# TinyG3DPrinterController.net
KiCad netlist of a schematic drawn in EAGLE
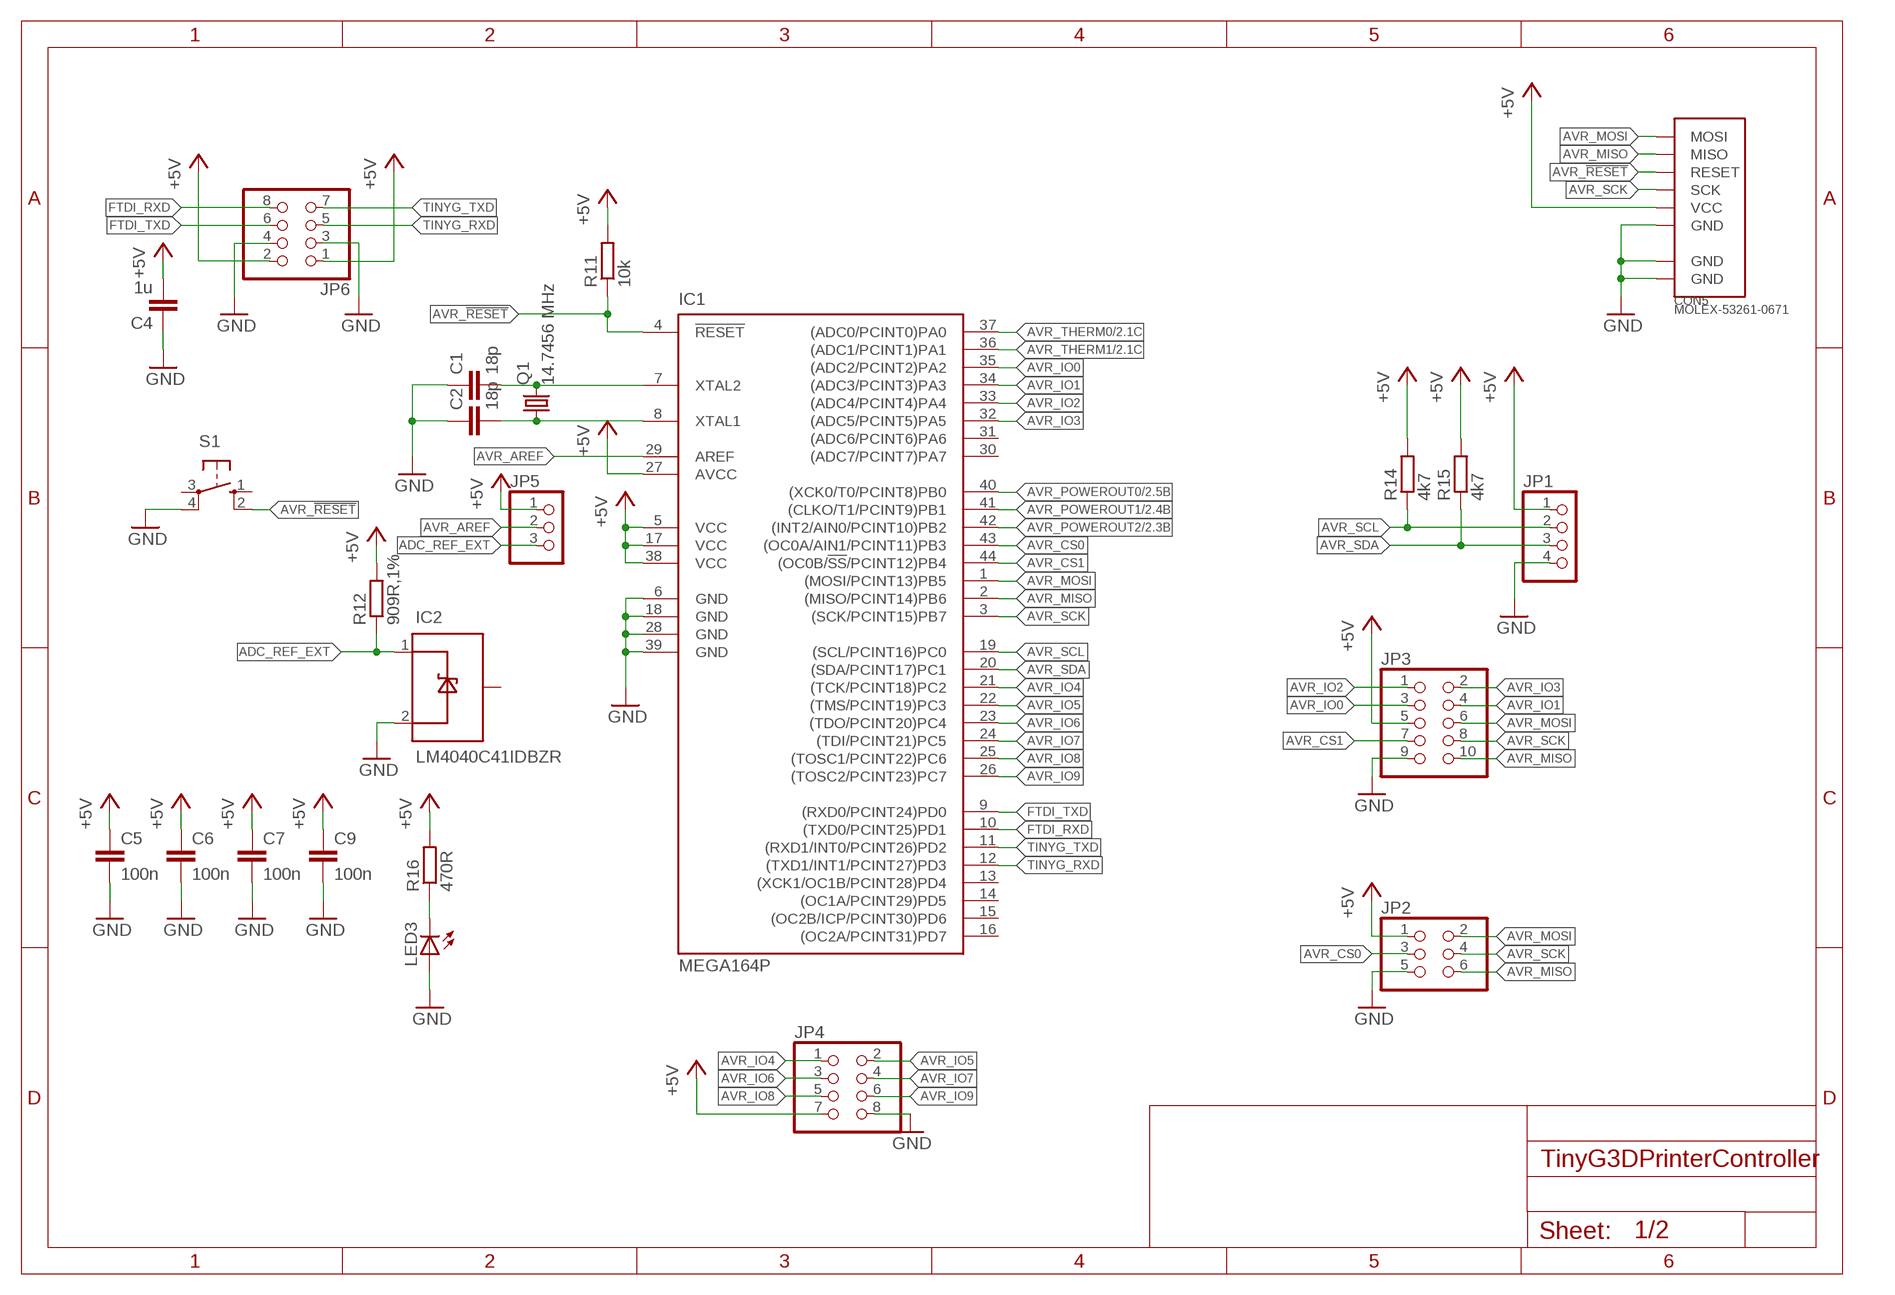
[diagram p0: schematic, sheet 1]
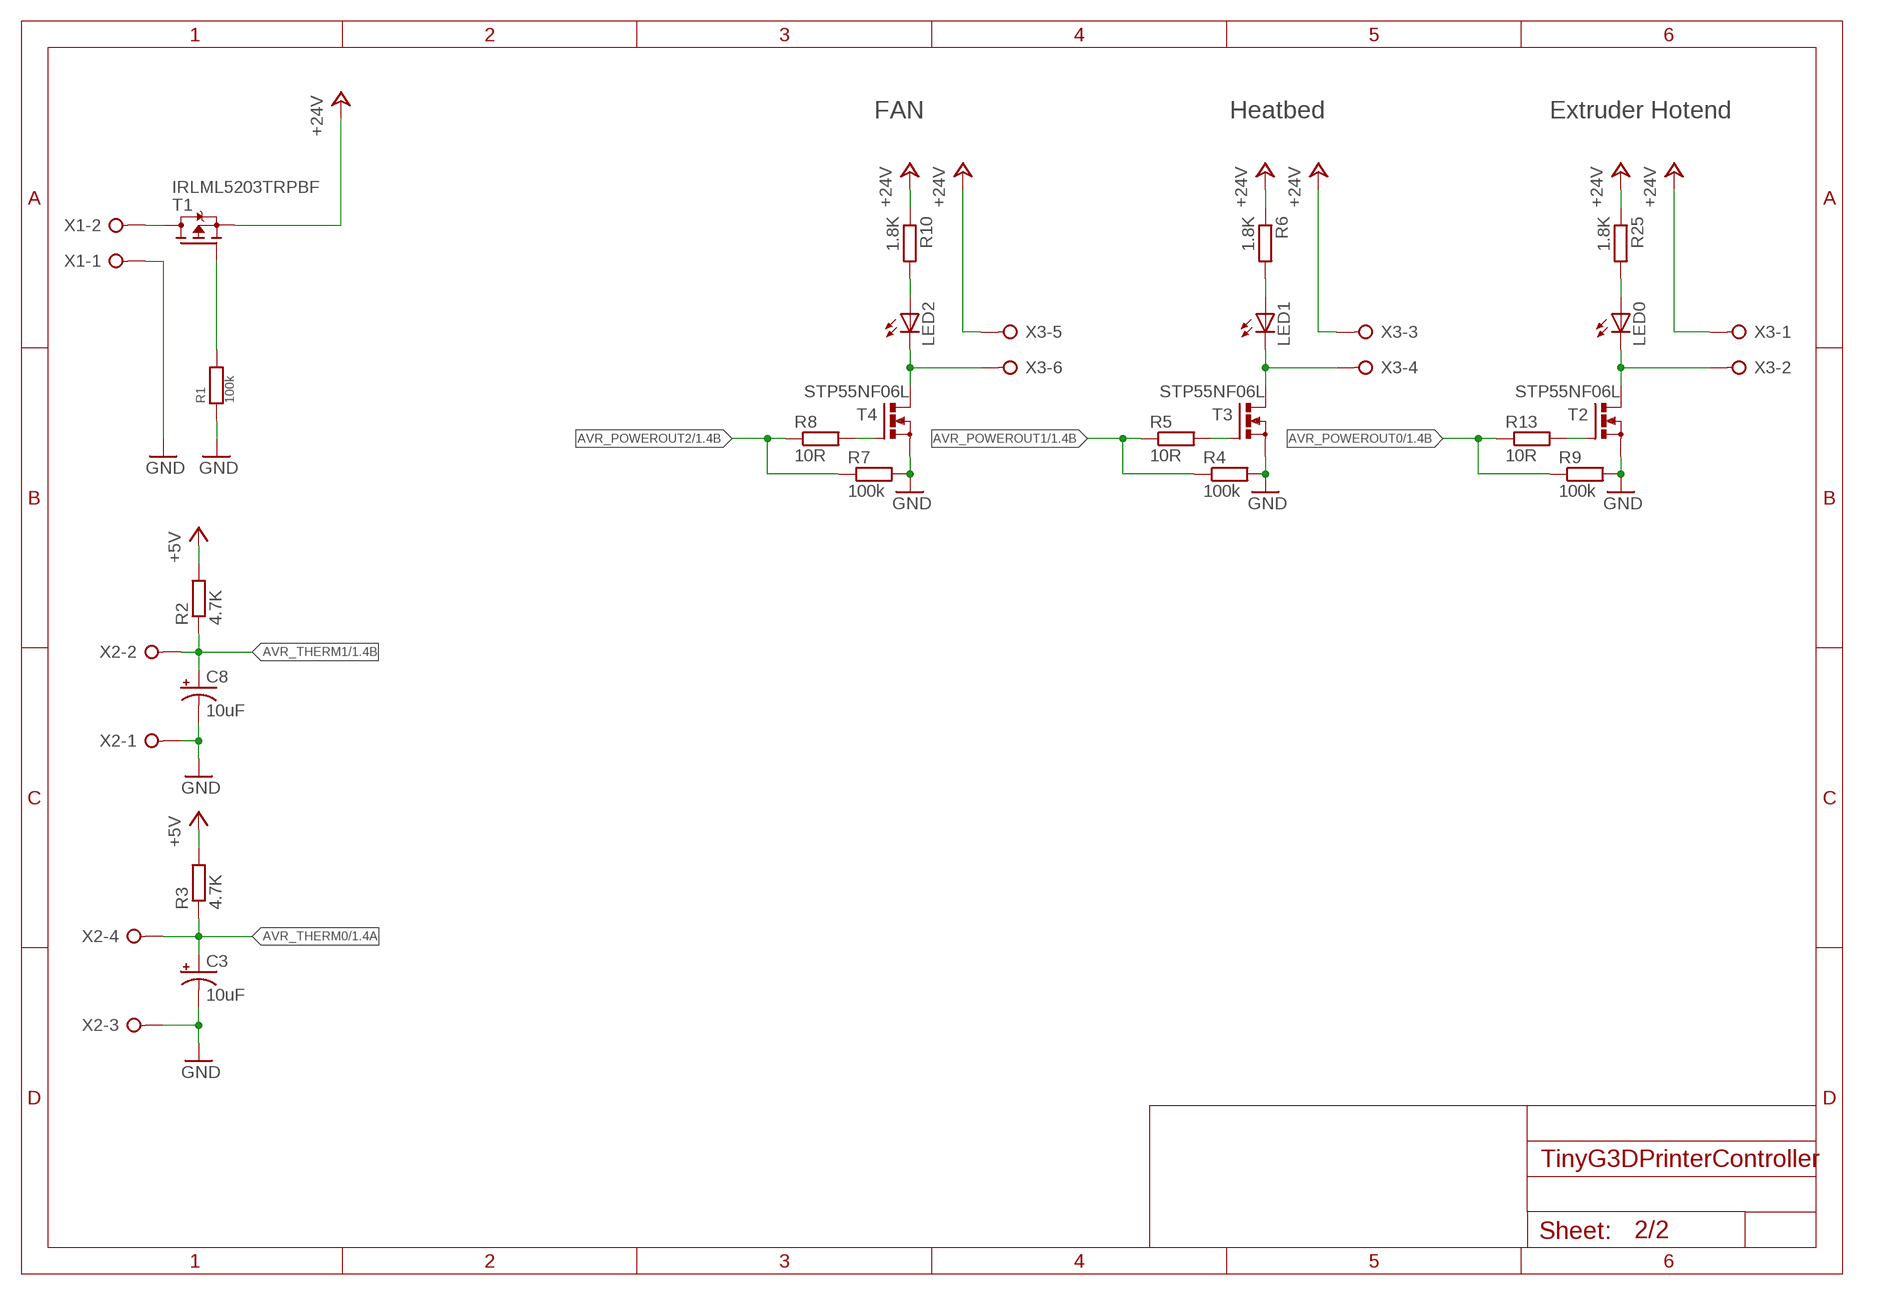
[diagram p1: schematic, sheet 2]

(export (version "E")
  (design (tool "Eeschema 10.0.6"))
  (components
    (comp (ref "C1")
      (value "18p")
      (footprint "eagle-import:C0603K")
      (libsource (lib "eagle-import") (part "C-EUC0603K"))
    )
    (comp (ref "C2")
      (value "18p")
      (footprint "eagle-import:C0603K")
      (libsource (lib "eagle-import") (part "C-EUC0603K"))
    )
    (comp (ref "C4")
      (value "1u")
      (footprint "eagle-import:C1206K")
      (libsource (lib "eagle-import") (part "C-EUC1206K"))
    )
    (comp (ref "C5")
      (value "100n")
      (footprint "eagle-import:C0603K")
      (libsource (lib "eagle-import") (part "C-EUC0603K"))
    )
    (comp (ref "C6")
      (value "100n")
      (footprint "eagle-import:C0603K")
      (libsource (lib "eagle-import") (part "C-EUC0603K"))
    )
    (comp (ref "C7")
      (value "100n")
      (footprint "eagle-import:C0603K")
      (libsource (lib "eagle-import") (part "C-EUC0603K"))
    )
    (comp (ref "C9")
      (value "100n")
      (footprint "eagle-import:C0603K")
      (libsource (lib "eagle-import") (part "C-EUC0603K"))
    )
    (comp (ref "CON5")
      (value "MOLEX-53261-0671")
      (footprint "eagle-import:MOLEX-53261-0671")
      (libsource (lib "eagle-import") (part "MOLEX-53261-0671"))
    )
    (comp (ref "IC1")
      (value "MEGA164P")
      (footprint "eagle-import:TQFP44")
      (libsource (lib "eagle-import") (part "MEGA164P/324P/644P-AU"))
    )
    (comp (ref "IC2")
      (value "LM4040C41IDBZR")
      (footprint "eagle-import:SOT-23-3")
      (libsource (lib "eagle-import") (part "LM4040C41IDBZR"))
    )
    (comp (ref "JP1")
      (value "PINHD-1X4")
      (footprint "eagle-import:1X04")
      (libsource (lib "eagle-import") (part "PINHD-1X4"))
    )
    (comp (ref "JP2")
      (value "PINHD-2X3")
      (footprint "eagle-import:2X03")
      (libsource (lib "eagle-import") (part "PINHD-2X3"))
    )
    (comp (ref "JP3")
      (value "PINHD-2X5")
      (footprint "eagle-import:2X05")
      (libsource (lib "eagle-import") (part "PINHD-2X5"))
    )
    (comp (ref "JP4")
      (value "PINHD-2X4")
      (footprint "eagle-import:2X04")
      (libsource (lib "eagle-import") (part "PINHD-2X4"))
    )
    (comp (ref "JP5")
      (value "PINHD-1X3")
      (footprint "eagle-import:1X03")
      (libsource (lib "eagle-import") (part "PINHD-1X3"))
    )
    (comp (ref "JP6")
      (value "PINHD-2X4")
      (footprint "eagle-import:2X04")
      (libsource (lib "eagle-import") (part "PINHD-2X4"))
    )
    (comp (ref "LED3")
      (value "LEDCHIP-LED0805")
      (footprint "eagle-import:CHIP-LED0805")
      (libsource (lib "eagle-import") (part "LEDCHIP-LED0805"))
    )
    (comp (ref "Q1")
      (value "14.7456 MHz")
      (footprint "eagle-import:CRYSTAL_2P_5MMX3.2MM")
      (libsource (lib "eagle-import") (part "7A-14.7456MAAJ-T-SMD_CRYSTAL"))
    )
    (comp (ref "R11")
      (value "10k")
      (footprint "eagle-import:R0603")
      (libsource (lib "eagle-import") (part "R-EU_R0603"))
    )
    (comp (ref "R12")
      (value "909R,1%")
      (footprint "eagle-import:R0603")
      (libsource (lib "eagle-import") (part "R-EU_R0603"))
    )
    (comp (ref "R14")
      (value "4k7")
      (footprint "eagle-import:R0603")
      (libsource (lib "eagle-import") (part "R-EU_R0603"))
    )
    (comp (ref "R15")
      (value "4k7")
      (footprint "eagle-import:R0603")
      (libsource (lib "eagle-import") (part "R-EU_R0603"))
    )
    (comp (ref "R16")
      (value "470R")
      (footprint "eagle-import:R0603")
      (libsource (lib "eagle-import") (part "R-EU_R0603"))
    )
    (comp (ref "S1")
      (value "10-XX")
      (footprint "eagle-import:B3F-10XX")
      (fields (field (name "MPN") "B3F-1000"))
      (libsource (lib "eagle-import") (part "10-XX"))
    )
    (comp (ref "C3")
      (value "10uF")
      (footprint "eagle-import:153CLV-0405")
      (libsource (lib "eagle-import") (part "CPOL-US153CLV-0405"))
    )
    (comp (ref "C8")
      (value "10uF")
      (footprint "eagle-import:153CLV-0405")
      (libsource (lib "eagle-import") (part "CPOL-US153CLV-0405"))
    )
    (comp (ref "LED0")
      (value "LEDCHIP-LED0805")
      (footprint "eagle-import:CHIP-LED0805")
      (libsource (lib "eagle-import") (part "LEDCHIP-LED0805"))
    )
    (comp (ref "LED1")
      (value "LEDCHIP-LED0805")
      (footprint "eagle-import:CHIP-LED0805")
      (libsource (lib "eagle-import") (part "LEDCHIP-LED0805"))
    )
    (comp (ref "LED2")
      (value "LEDCHIP-LED0805")
      (footprint "eagle-import:CHIP-LED0805")
      (libsource (lib "eagle-import") (part "LEDCHIP-LED0805"))
    )
    (comp (ref "R1")
      (value "100k")
      (footprint "eagle-import:R0603")
      (libsource (lib "eagle-import") (part "R0603"))
    )
    (comp (ref "R2")
      (value "4.7K")
      (footprint "eagle-import:R0603")
      (libsource (lib "eagle-import") (part "R-EU_R0603"))
    )
    (comp (ref "R3")
      (value "4.7K")
      (footprint "eagle-import:R0603")
      (libsource (lib "eagle-import") (part "R-EU_R0603"))
    )
    (comp (ref "R4")
      (value "100k")
      (footprint "eagle-import:R0603")
      (libsource (lib "eagle-import") (part "R-EU_R0603"))
    )
    (comp (ref "R5")
      (value "10R")
      (footprint "eagle-import:R0603")
      (libsource (lib "eagle-import") (part "R-EU_R0603"))
    )
    (comp (ref "R6")
      (value "1.8K")
      (footprint "eagle-import:R0603")
      (libsource (lib "eagle-import") (part "R-EU_R0603"))
    )
    (comp (ref "R7")
      (value "100k")
      (footprint "eagle-import:R0603")
      (libsource (lib "eagle-import") (part "R-EU_R0603"))
    )
    (comp (ref "R8")
      (value "10R")
      (footprint "eagle-import:R0603")
      (libsource (lib "eagle-import") (part "R-EU_R0603"))
    )
    (comp (ref "R9")
      (value "100k")
      (footprint "eagle-import:R0603")
      (libsource (lib "eagle-import") (part "R-EU_R0603"))
    )
    (comp (ref "R10")
      (value "1.8K")
      (footprint "eagle-import:R0603")
      (libsource (lib "eagle-import") (part "R-EU_R0603"))
    )
    (comp (ref "R13")
      (value "10R")
      (footprint "eagle-import:R0603")
      (libsource (lib "eagle-import") (part "R-EU_R0603"))
    )
    (comp (ref "R25")
      (value "1.8K")
      (footprint "eagle-import:R0603")
      (libsource (lib "eagle-import") (part "R-EU_R0603"))
    )
    (comp (ref "T1")
      (value "IRLML5203TRPBF")
      (footprint "eagle-import:SOT23")
      (libsource (lib "eagle-import") (part "IRLML5203TRPBF"))
    )
    (comp (ref "T2")
      (value "STP55NF06L")
      (footprint "eagle-import:TO220BV")
      (libsource (lib "eagle-import") (part "IRF512"))
    )
    (comp (ref "T3")
      (value "STP55NF06L")
      (footprint "eagle-import:TO220BV")
      (libsource (lib "eagle-import") (part "IRF512"))
    )
    (comp (ref "T4")
      (value "STP55NF06L")
      (footprint "eagle-import:TO220BV")
      (libsource (lib "eagle-import") (part "IRF512"))
    )
    (comp (ref "X1")
      (value "W237-02P")
      (footprint "eagle-import:W237-132")
      (libsource (lib "eagle-import") (part "W237-02P"))
    )
    (comp (ref "X2")
      (value "W237-04P")
      (footprint "eagle-import:W237-4P")
      (libsource (lib "eagle-import") (part "W237-04P"))
    )
    (comp (ref "X3")
      (value "W237-06P")
      (footprint "eagle-import:W237-6P")
      (libsource (lib "eagle-import") (part "W237-06P"))
    )
  )
  (nets
    (net (code "1") (name "+5V") (class "Default")
      (node (ref "C4") (pin "2") (pinfunction "2_2") (pintype "passive"))
      (node (ref "C5") (pin "1") (pinfunction "1_1") (pintype "passive"))
      (node (ref "C6") (pin "1") (pinfunction "1_1") (pintype "passive"))
      (node (ref "C7") (pin "1") (pinfunction "1_1") (pintype "passive"))
      (node (ref "C9") (pin "1") (pinfunction "1_1") (pintype "passive"))
      (node (ref "CON5") (pin "5") (pinfunction "VCC_5") (pintype "bidirectional"))
      (node (ref "IC1") (pin "17") (pinfunction "VCC_17") (pintype "power_in"))
      (node (ref "IC1") (pin "27") (pinfunction "AVCC_27") (pintype "power_in"))
      (node (ref "IC1") (pin "38") (pinfunction "VCC_38") (pintype "power_in"))
      (node (ref "IC1") (pin "5") (pinfunction "VCC_5") (pintype "power_in"))
      (node (ref "JP1") (pin "1") (pinfunction "1_1") (pintype "passive"))
      (node (ref "JP2") (pin "1") (pinfunction "1_1") (pintype "passive"))
      (node (ref "JP3") (pin "5") (pinfunction "5_5") (pintype "passive"))
      (node (ref "JP4") (pin "7") (pinfunction "7_7") (pintype "passive"))
      (node (ref "JP5") (pin "1") (pinfunction "1_1") (pintype "passive"))
      (node (ref "JP6") (pin "1") (pinfunction "1_1") (pintype "passive"))
      (node (ref "JP6") (pin "2") (pinfunction "2_2") (pintype "passive"))
      (node (ref "R11") (pin "2") (pinfunction "2_2") (pintype "passive"))
      (node (ref "R12") (pin "2") (pinfunction "2_2") (pintype "passive"))
      (node (ref "R14") (pin "2") (pinfunction "2_2") (pintype "passive"))
      (node (ref "R15") (pin "2") (pinfunction "2_2") (pintype "passive"))
      (node (ref "R16") (pin "2") (pinfunction "2_2") (pintype "passive"))
      (node (ref "R2") (pin "2") (pinfunction "2_2") (pintype "passive"))
      (node (ref "R3") (pin "2") (pinfunction "2_2") (pintype "passive"))
    )
    (net (code "2") (name "+24V") (class "Default")
      (node (ref "R10") (pin "1") (pinfunction "1_1") (pintype "passive"))
      (node (ref "R25") (pin "1") (pinfunction "1_1") (pintype "passive"))
      (node (ref "R6") (pin "1") (pinfunction "1_1") (pintype "passive"))
      (node (ref "T1") (pin "2") (pinfunction "S_2") (pintype "passive"))
      (node (ref "X3") (pin "1") (pinfunction "KL_1") (pintype "passive"))
      (node (ref "X3") (pin "3") (pinfunction "KL_3") (pintype "passive"))
      (node (ref "X3") (pin "5") (pinfunction "KL_5") (pintype "passive"))
    )
    (net (code "3") (name "ADC_REF_EXT") (class "Default")
      (node (ref "IC2") (pin "1") (pinfunction "1_1") (pintype "bidirectional"))
      (node (ref "JP5") (pin "3") (pinfunction "3_3") (pintype "passive"))
      (node (ref "R12") (pin "1") (pinfunction "1_1") (pintype "passive"))
    )
    (net (code "4") (name "AVR_AREF") (class "Default")
      (node (ref "IC1") (pin "29") (pinfunction "AREF_29") (pintype "power_in"))
      (node (ref "JP5") (pin "2") (pinfunction "2_2") (pintype "passive"))
    )
    (net (code "5") (name "AVR_CS0") (class "Default")
      (node (ref "IC1") (pin "43") (pinfunction "(OC0A/AIN1/PCINT11)PB3_43") (pintype "bidirectional"))
      (node (ref "JP2") (pin "3") (pinfunction "3_3") (pintype "passive"))
    )
    (net (code "6") (name "AVR_CS1") (class "Default")
      (node (ref "IC1") (pin "44") (pinfunction "(OC0B/~{SS}/PCINT12)PB4_44") (pintype "bidirectional"))
      (node (ref "JP3") (pin "7") (pinfunction "7_7") (pintype "passive"))
    )
    (net (code "7") (name "AVR_IO0") (class "Default")
      (node (ref "IC1") (pin "35") (pinfunction "(ADC2/PCINT2)PA2_35") (pintype "bidirectional"))
      (node (ref "JP3") (pin "3") (pinfunction "3_3") (pintype "passive"))
    )
    (net (code "8") (name "AVR_IO1") (class "Default")
      (node (ref "IC1") (pin "34") (pinfunction "(ADC3/PCINT3)PA3_34") (pintype "bidirectional"))
      (node (ref "JP3") (pin "4") (pinfunction "4_4") (pintype "passive"))
    )
    (net (code "9") (name "AVR_IO2") (class "Default")
      (node (ref "IC1") (pin "33") (pinfunction "(ADC4/PCINT4)PA4_33") (pintype "bidirectional"))
      (node (ref "JP3") (pin "1") (pinfunction "1_1") (pintype "passive"))
    )
    (net (code "10") (name "AVR_IO3") (class "Default")
      (node (ref "IC1") (pin "32") (pinfunction "(ADC5/PCINT5)PA5_32") (pintype "bidirectional"))
      (node (ref "JP3") (pin "2") (pinfunction "2_2") (pintype "passive"))
    )
    (net (code "11") (name "AVR_IO4") (class "Default")
      (node (ref "IC1") (pin "21") (pinfunction "(TCK/PCINT18)PC2_21") (pintype "bidirectional"))
      (node (ref "JP4") (pin "1") (pinfunction "1_1") (pintype "passive"))
    )
    (net (code "12") (name "AVR_IO5") (class "Default")
      (node (ref "IC1") (pin "22") (pinfunction "(TMS/PCINT19)PC3_22") (pintype "bidirectional"))
      (node (ref "JP4") (pin "2") (pinfunction "2_2") (pintype "passive"))
    )
    (net (code "13") (name "AVR_IO6") (class "Default")
      (node (ref "IC1") (pin "23") (pinfunction "(TDO/PCINT20)PC4_23") (pintype "bidirectional"))
      (node (ref "JP4") (pin "3") (pinfunction "3_3") (pintype "passive"))
    )
    (net (code "14") (name "AVR_IO7") (class "Default")
      (node (ref "IC1") (pin "24") (pinfunction "(TDI/PCINT21)PC5_24") (pintype "bidirectional"))
      (node (ref "JP4") (pin "4") (pinfunction "4_4") (pintype "passive"))
    )
    (net (code "15") (name "AVR_IO8") (class "Default")
      (node (ref "IC1") (pin "25") (pinfunction "(TOSC1/PCINT22)PC6_25") (pintype "bidirectional"))
      (node (ref "JP4") (pin "5") (pinfunction "5_5") (pintype "passive"))
    )
    (net (code "16") (name "AVR_IO9") (class "Default")
      (node (ref "IC1") (pin "26") (pinfunction "(TOSC2/PCINT23)PC7_26") (pintype "bidirectional"))
      (node (ref "JP4") (pin "6") (pinfunction "6_6") (pintype "passive"))
    )
    (net (code "17") (name "AVR_MISO") (class "Default")
      (node (ref "CON5") (pin "2") (pinfunction "MISO_2") (pintype "bidirectional"))
      (node (ref "IC1") (pin "2") (pinfunction "(MISO/PCINT14)PB6_2") (pintype "bidirectional"))
      (node (ref "JP2") (pin "6") (pinfunction "6_6") (pintype "passive"))
      (node (ref "JP3") (pin "10") (pinfunction "10_10") (pintype "passive"))
    )
    (net (code "18") (name "AVR_MOSI") (class "Default")
      (node (ref "CON5") (pin "1") (pinfunction "MOSI_1") (pintype "bidirectional"))
      (node (ref "IC1") (pin "1") (pinfunction "(MOSI/PCINT13)PB5_1") (pintype "bidirectional"))
      (node (ref "JP2") (pin "2") (pinfunction "2_2") (pintype "passive"))
      (node (ref "JP3") (pin "6") (pinfunction "6_6") (pintype "passive"))
    )
    (net (code "19") (name "AVR_POWEROUT0") (class "Default")
      (node (ref "IC1") (pin "40") (pinfunction "(XCK0/T0/PCINT8)PB0_40") (pintype "bidirectional"))
      (node (ref "R13") (pin "1") (pinfunction "1_1") (pintype "passive"))
      (node (ref "R9") (pin "1") (pinfunction "1_1") (pintype "passive"))
    )
    (net (code "20") (name "AVR_POWEROUT1") (class "Default")
      (node (ref "IC1") (pin "41") (pinfunction "(CLKO/T1/PCINT9)PB1_41") (pintype "bidirectional"))
      (node (ref "R4") (pin "1") (pinfunction "1_1") (pintype "passive"))
      (node (ref "R5") (pin "1") (pinfunction "1_1") (pintype "passive"))
    )
    (net (code "21") (name "AVR_POWEROUT2") (class "Default")
      (node (ref "IC1") (pin "42") (pinfunction "(INT2/AIN0/PCINT10)PB2_42") (pintype "bidirectional"))
      (node (ref "R7") (pin "1") (pinfunction "1_1") (pintype "passive"))
      (node (ref "R8") (pin "1") (pinfunction "1_1") (pintype "passive"))
    )
    (net (code "22") (name "AVR_SCK") (class "Default")
      (node (ref "CON5") (pin "4") (pinfunction "SCK_4") (pintype "bidirectional"))
      (node (ref "IC1") (pin "3") (pinfunction "(SCK/PCINT15)PB7_3") (pintype "bidirectional"))
      (node (ref "JP2") (pin "4") (pinfunction "4_4") (pintype "passive"))
      (node (ref "JP3") (pin "8") (pinfunction "8_8") (pintype "passive"))
    )
    (net (code "23") (name "AVR_SCL") (class "Default")
      (node (ref "IC1") (pin "19") (pinfunction "(SCL/PCINT16)PC0_19") (pintype "bidirectional"))
      (node (ref "JP1") (pin "2") (pinfunction "2_2") (pintype "passive"))
      (node (ref "R14") (pin "1") (pinfunction "1_1") (pintype "passive"))
    )
    (net (code "24") (name "AVR_SDA") (class "Default")
      (node (ref "IC1") (pin "20") (pinfunction "(SDA/PCINT17)PC1_20") (pintype "bidirectional"))
      (node (ref "JP1") (pin "3") (pinfunction "3_3") (pintype "passive"))
      (node (ref "R15") (pin "1") (pinfunction "1_1") (pintype "passive"))
    )
    (net (code "25") (name "AVR_THERM0") (class "Default")
      (node (ref "C3") (pin "+") (pinfunction "+_+") (pintype "passive"))
      (node (ref "IC1") (pin "37") (pinfunction "(ADC0/PCINT0)PA0_37") (pintype "bidirectional"))
      (node (ref "R3") (pin "1") (pinfunction "1_1") (pintype "passive"))
      (node (ref "X2") (pin "4") (pinfunction "KL_4") (pintype "passive"))
    )
    (net (code "26") (name "AVR_THERM1") (class "Default")
      (node (ref "C8") (pin "+") (pinfunction "+_+") (pintype "passive"))
      (node (ref "IC1") (pin "36") (pinfunction "(ADC1/PCINT1)PA1_36") (pintype "bidirectional"))
      (node (ref "R2") (pin "1") (pinfunction "1_1") (pintype "passive"))
      (node (ref "X2") (pin "2") (pinfunction "KL_2") (pintype "passive"))
    )
    (net (code "27") (name "AVR_~{RESET}") (class "Default")
      (node (ref "CON5") (pin "3") (pinfunction "RESET_3") (pintype "bidirectional"))
      (node (ref "IC1") (pin "4") (pinfunction "~{RESET}_4") (pintype "input"))
      (node (ref "R11") (pin "1") (pinfunction "1_1") (pintype "passive"))
      (node (ref "S1") (pin "2") (pinfunction "S1_2") (pintype "passive"))
    )
    (net (code "28") (name "FTDI_RXD") (class "Default")
      (node (ref "IC1") (pin "10") (pinfunction "(TXD0/PCINT25)PD1_10") (pintype "bidirectional"))
      (node (ref "JP6") (pin "8") (pinfunction "8_8") (pintype "passive"))
    )
    (net (code "29") (name "FTDI_TXD") (class "Default")
      (node (ref "IC1") (pin "9") (pinfunction "(RXD0/PCINT24)PD0_9") (pintype "bidirectional"))
      (node (ref "JP6") (pin "6") (pinfunction "6_6") (pintype "passive"))
    )
    (net (code "30") (name "GND") (class "Default")
      (node (ref "C1") (pin "1") (pinfunction "1_1") (pintype "passive"))
      (node (ref "C2") (pin "1") (pinfunction "1_1") (pintype "passive"))
      (node (ref "C3") (pin "-") (pinfunction "-_-") (pintype "passive"))
      (node (ref "C4") (pin "1") (pinfunction "1_1") (pintype "passive"))
      (node (ref "C5") (pin "2") (pinfunction "2_2") (pintype "passive"))
      (node (ref "C6") (pin "2") (pinfunction "2_2") (pintype "passive"))
      (node (ref "C7") (pin "2") (pinfunction "2_2") (pintype "passive"))
      (node (ref "C8") (pin "-") (pinfunction "-_-") (pintype "passive"))
      (node (ref "C9") (pin "2") (pinfunction "2_2") (pintype "passive"))
      (node (ref "CON5") (pin "6") (pinfunction "GND_6") (pintype "bidirectional"))
      (node (ref "CON5") (pin "GND@1") (pinfunction "GND_GND@1") (pintype "power_in"))
      (node (ref "CON5") (pin "GND@2") (pinfunction "GND_GND@2") (pintype "power_in"))
      (node (ref "IC1") (pin "18") (pinfunction "GND_18") (pintype "power_in"))
      (node (ref "IC1") (pin "28") (pinfunction "GND_28") (pintype "power_in"))
      (node (ref "IC1") (pin "39") (pinfunction "GND_39") (pintype "power_in"))
      (node (ref "IC1") (pin "6") (pinfunction "GND_6") (pintype "power_in"))
      (node (ref "IC2") (pin "2") (pinfunction "2_2") (pintype "bidirectional"))
      (node (ref "JP1") (pin "4") (pinfunction "4_4") (pintype "passive"))
      (node (ref "JP2") (pin "5") (pinfunction "5_5") (pintype "passive"))
      (node (ref "JP3") (pin "9") (pinfunction "9_9") (pintype "passive"))
      (node (ref "JP4") (pin "8") (pinfunction "8_8") (pintype "passive"))
      (node (ref "JP6") (pin "3") (pinfunction "3_3") (pintype "passive"))
      (node (ref "JP6") (pin "4") (pinfunction "4_4") (pintype "passive"))
      (node (ref "LED3") (pin "A") (pinfunction "A_A") (pintype "passive"))
      (node (ref "R1") (pin "1") (pinfunction "P$1_1") (pintype "passive"))
      (node (ref "R4") (pin "2") (pinfunction "2_2") (pintype "passive"))
      (node (ref "R7") (pin "2") (pinfunction "2_2") (pintype "passive"))
      (node (ref "R9") (pin "2") (pinfunction "2_2") (pintype "passive"))
      (node (ref "S1") (pin "4") (pinfunction "P1_4") (pintype "passive"))
      (node (ref "T2") (pin "S") (pinfunction "S_S") (pintype "passive"))
      (node (ref "T3") (pin "S") (pinfunction "S_S") (pintype "passive"))
      (node (ref "T4") (pin "S") (pinfunction "S_S") (pintype "passive"))
      (node (ref "X1") (pin "1") (pinfunction "KL_1") (pintype "passive"))
      (node (ref "X2") (pin "1") (pinfunction "KL_1") (pintype "passive"))
      (node (ref "X2") (pin "3") (pinfunction "KL_3") (pintype "passive"))
    )
    (net (code "31") (name "Net-(IC1-XTAL1)") (class "Default")
      (node (ref "C2") (pin "2") (pinfunction "2_2") (pintype "passive"))
      (node (ref "IC1") (pin "8") (pinfunction "XTAL1_8") (pintype "input"))
      (node (ref "Q1") (pin "P$1") (pinfunction "1_P$1") (pintype "passive"))
    )
    (net (code "32") (name "Net-(IC1-XTAL2)") (class "Default")
      (node (ref "C1") (pin "2") (pinfunction "2_2") (pintype "passive"))
      (node (ref "IC1") (pin "7") (pinfunction "XTAL2_7") (pintype "output"))
      (node (ref "Q1") (pin "P$2") (pinfunction "2_P$2") (pintype "passive"))
    )
    (net (code "33") (name "Net-(LED0-PadA)") (class "Default")
      (node (ref "LED0") (pin "A") (pinfunction "A_A") (pintype "passive"))
      (node (ref "R25") (pin "2") (pinfunction "2_2") (pintype "passive"))
    )
    (net (code "34") (name "Net-(LED1-PadA)") (class "Default")
      (node (ref "LED1") (pin "A") (pinfunction "A_A") (pintype "passive"))
      (node (ref "R6") (pin "2") (pinfunction "2_2") (pintype "passive"))
    )
    (net (code "35") (name "Net-(LED2-PadA)") (class "Default")
      (node (ref "LED2") (pin "A") (pinfunction "A_A") (pintype "passive"))
      (node (ref "R10") (pin "2") (pinfunction "2_2") (pintype "passive"))
    )
    (net (code "36") (name "Net-(LED3-PadC)") (class "Default")
      (node (ref "LED3") (pin "C") (pinfunction "C_C") (pintype "passive"))
      (node (ref "R16") (pin "1") (pinfunction "1_1") (pintype "passive"))
    )
    (net (code "37") (name "Net-(R1-P$2)") (class "Default")
      (node (ref "R1") (pin "2") (pinfunction "P$2_2") (pintype "passive"))
      (node (ref "T1") (pin "1") (pinfunction "G_1") (pintype "passive"))
    )
    (net (code "38") (name "Net-(R5-Pad2)") (class "Default")
      (node (ref "R5") (pin "2") (pinfunction "2_2") (pintype "passive"))
      (node (ref "T3") (pin "G") (pinfunction "G_G") (pintype "passive"))
    )
    (net (code "39") (name "Net-(R8-Pad2)") (class "Default")
      (node (ref "R8") (pin "2") (pinfunction "2_2") (pintype "passive"))
      (node (ref "T4") (pin "G") (pinfunction "G_G") (pintype "passive"))
    )
    (net (code "40") (name "Net-(R13-Pad2)") (class "Default")
      (node (ref "R13") (pin "2") (pinfunction "2_2") (pintype "passive"))
      (node (ref "T2") (pin "G") (pinfunction "G_G") (pintype "passive"))
    )
    (net (code "41") (name "Net-(T1-D)") (class "Default")
      (node (ref "T1") (pin "3") (pinfunction "D_3") (pintype "passive"))
      (node (ref "X1") (pin "2") (pinfunction "KL_2") (pintype "passive"))
    )
    (net (code "42") (name "Net-(X3B-KL)") (class "Default")
      (node (ref "LED0") (pin "C") (pinfunction "C_C") (pintype "passive"))
      (node (ref "T2") (pin "D") (pinfunction "D_D") (pintype "passive"))
      (node (ref "X3") (pin "2") (pinfunction "KL_2") (pintype "passive"))
    )
    (net (code "43") (name "Net-(X3D-KL)") (class "Default")
      (node (ref "LED1") (pin "C") (pinfunction "C_C") (pintype "passive"))
      (node (ref "T3") (pin "D") (pinfunction "D_D") (pintype "passive"))
      (node (ref "X3") (pin "4") (pinfunction "KL_4") (pintype "passive"))
    )
    (net (code "44") (name "Net-(X3F-KL)") (class "Default")
      (node (ref "LED2") (pin "C") (pinfunction "C_C") (pintype "passive"))
      (node (ref "T4") (pin "D") (pinfunction "D_D") (pintype "passive"))
      (node (ref "X3") (pin "6") (pinfunction "KL_6") (pintype "passive"))
    )
    (net (code "45") (name "TINYG_RXD") (class "Default")
      (node (ref "IC1") (pin "12") (pinfunction "(TXD1/INT1/PCINT27)PD3_12") (pintype "bidirectional"))
      (node (ref "JP6") (pin "5") (pinfunction "5_5") (pintype "passive"))
    )
    (net (code "46") (name "TINYG_TXD") (class "Default")
      (node (ref "IC1") (pin "11") (pinfunction "(RXD1/INT0/PCINT26)PD2_11") (pintype "bidirectional"))
      (node (ref "JP6") (pin "7") (pinfunction "7_7") (pintype "passive"))
    )
    (net (code "47") (name "unconnected-(IC1-(ADC6{slash}PCINT6)PA6-Pad31)") (class "Default")
      (node (ref "IC1") (pin "31") (pinfunction "(ADC6/PCINT6)PA6_31") (pintype "bidirectional"))
    )
    (net (code "48") (name "unconnected-(IC1-(ADC7{slash}PCINT7)PA7-Pad30)") (class "Default")
      (node (ref "IC1") (pin "30") (pinfunction "(ADC7/PCINT7)PA7_30") (pintype "bidirectional"))
    )
    (net (code "49") (name "unconnected-(IC1-(OC1A{slash}PCINT29)PD5-Pad14)") (class "Default")
      (node (ref "IC1") (pin "14") (pinfunction "(OC1A/PCINT29)PD5_14") (pintype "bidirectional"))
    )
    (net (code "50") (name "unconnected-(IC1-(OC2A{slash}PCINT31)PD7-Pad16)") (class "Default")
      (node (ref "IC1") (pin "16") (pinfunction "(OC2A/PCINT31)PD7_16") (pintype "bidirectional"))
    )
    (net (code "51") (name "unconnected-(IC1-(OC2B{slash}ICP{slash}PCINT30)PD6-Pad15)") (class "Default")
      (node (ref "IC1") (pin "15") (pinfunction "(OC2B/ICP/PCINT30)PD6_15") (pintype "bidirectional"))
    )
    (net (code "52") (name "unconnected-(IC1-(XCK1{slash}OC1B{slash}PCINT28)PD4-Pad13)") (class "Default")
      (node (ref "IC1") (pin "13") (pinfunction "(XCK1/OC1B/PCINT28)PD4_13") (pintype "bidirectional"))
    )
    (net (code "53") (name "unconnected-(IC2-Pad3)") (class "Default")
      (node (ref "IC2") (pin "3") (pinfunction "3_3") (pintype "bidirectional"))
    )
    (net (code "54") (name "unconnected-(S1-P-Pad3)") (class "Default")
      (node (ref "S1") (pin "3") (pinfunction "P_3") (pintype "passive"))
    )
    (net (code "55") (name "unconnected-(S1-S-Pad1)") (class "Default")
      (node (ref "S1") (pin "1") (pinfunction "S_1") (pintype "passive"))
    )
  )
)
